# Main_Board.net
KiCad netlist of a schematic drawn in Altium Designer
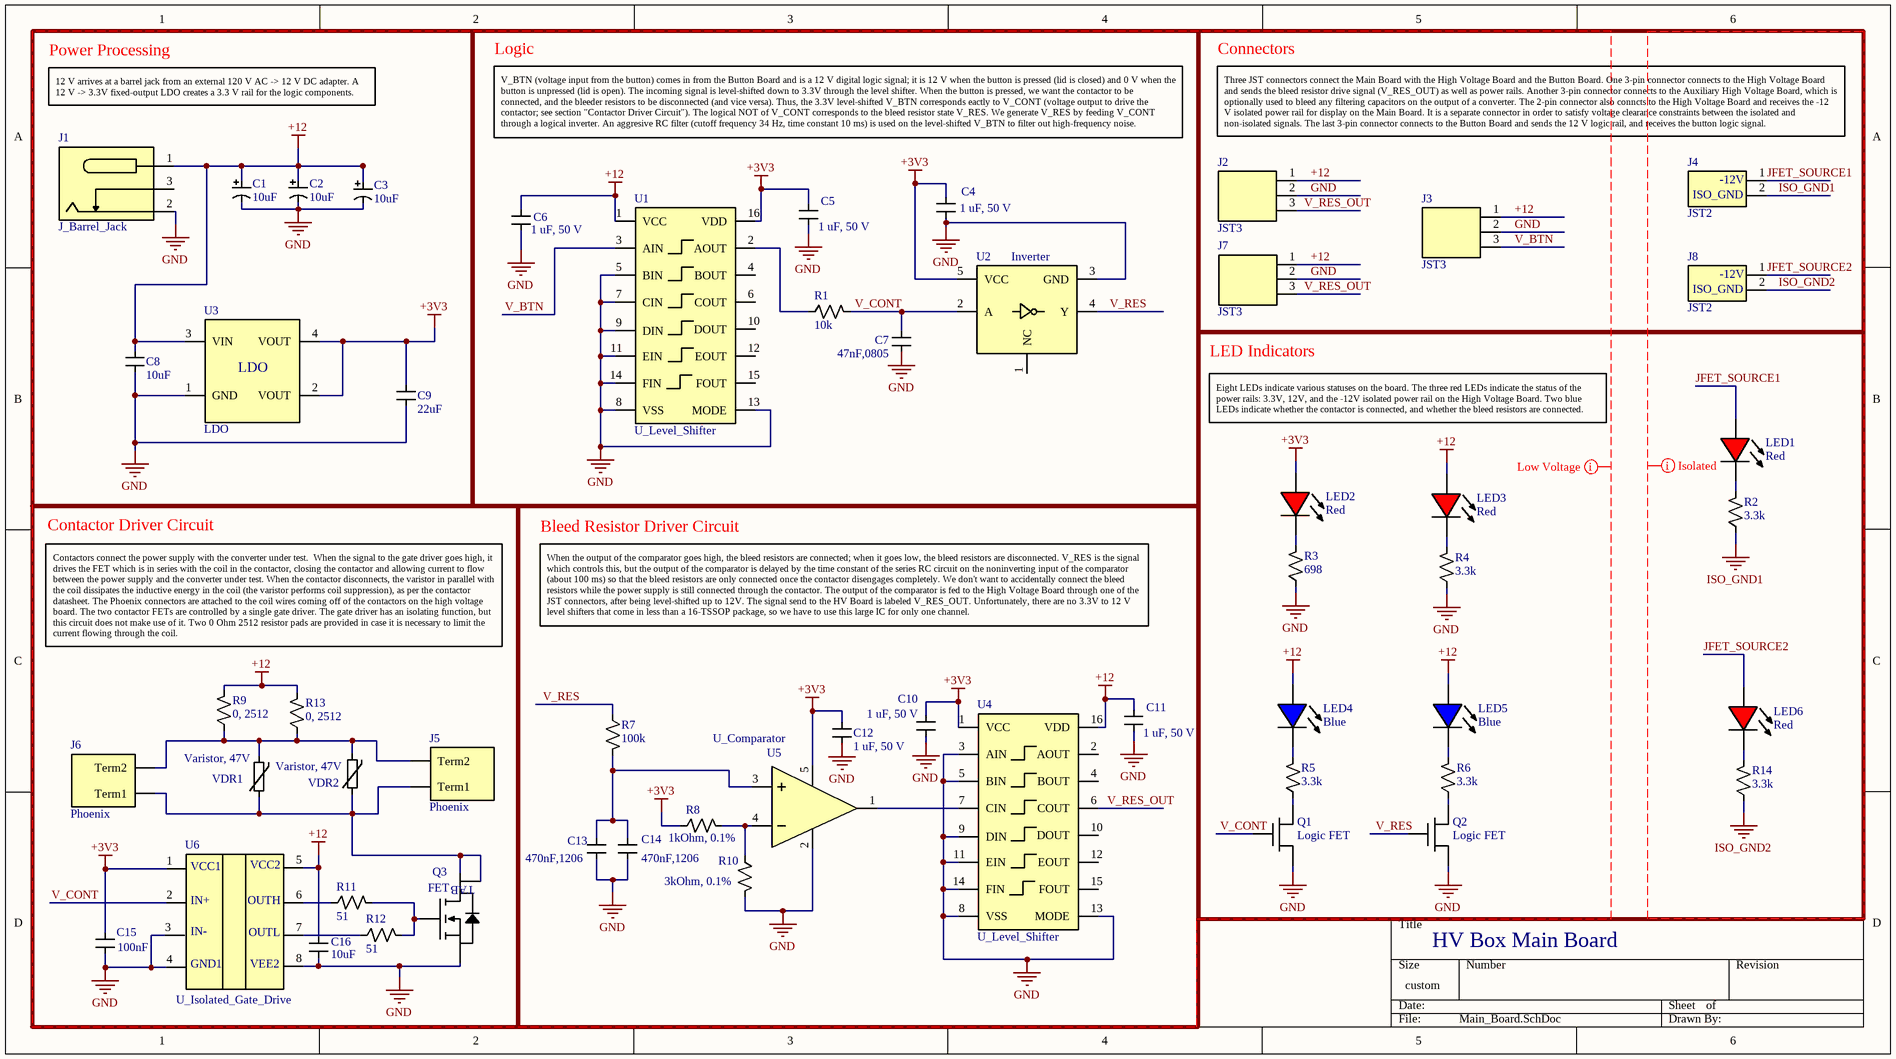
[diagram p0: Main_Board.SchDoc]

(export (version "E")
  (design (tool "Eeschema 10.0.6"))
  (components
    (comp (ref "C1")
      (value "10uF")
      (footprint "ALUM_CAP")
      (description "Capacitor SMD Aluminum Electrolytic 10 uF")
      (libsource (lib "Load_Bank_New_IntLib") (part "C_10uF_AlElec"))
    )
    (comp (ref "C2")
      (value "10uF")
      (footprint "ALUM_CAP")
      (description "Capacitor SMD Aluminum Electrolytic 10 uF")
      (libsource (lib "Load_Bank_New_IntLib") (part "C_10uF_AlElec"))
    )
    (comp (ref "C3")
      (value "10uF")
      (footprint "ALUM_CAP")
      (description "Capacitor SMD Aluminum Electrolytic 10 uF")
      (libsource (lib "Load_Bank_New_IntLib") (part "C_10uF_AlElec"))
    )
    (comp (ref "C4")
      (value "1 uF, 50 V")
      (footprint "0603_CAP")
      (description "Capacitor SMD MLCC 1 uF, 0603, 50 V")
      (libsource (lib "HV_Box_IntLib") (part "C_1uF_0603"))
    )
    (comp (ref "C5")
      (value "1 uF, 50 V")
      (footprint "0603_CAP")
      (description "Capacitor SMD MLCC 1 uF, 0603, 50 V")
      (libsource (lib "HV_Box_IntLib") (part "C_1uF_0603"))
    )
    (comp (ref "C6")
      (value "1 uF, 50 V")
      (footprint "0603_CAP")
      (description "Capacitor SMD MLCC 1 uF, 0603, 50 V")
      (libsource (lib "HV_Box_IntLib") (part "C_1uF_0603"))
    )
    (comp (ref "C7")
      (value "47nF,0805")
      (footprint "0805_CAP")
      (description "Capacitor SMD MLCC 47 nF 0805, C0G/NP0")
      (libsource (lib "HV_Box_IntLib") (part "C_47nF_0805"))
    )
    (comp (ref "C8")
      (value "10uF")
      (footprint "0805_CAP")
      (description "Capacitor SMD MLCC 10 uF 0805")
      (libsource (lib "Load_Bank_New_IntLib") (part "C_10uF_0805"))
    )
    (comp (ref "C9")
      (value "22uF")
      (footprint "1206_CAP")
      (description "Capacitor SMD MLCC 22 uF 25 V 1206")
      (libsource (lib "Load_Bank_New_IntLib") (part "C_22uF_1206"))
    )
    (comp (ref "C10")
      (value "1 uF, 50 V")
      (footprint "0603_CAP")
      (description "Capacitor SMD MLCC 1 uF, 0603, 50 V")
      (libsource (lib "HV_Box_IntLib") (part "C_1uF_0603"))
    )
    (comp (ref "C11")
      (value "1 uF, 50 V")
      (footprint "0603_CAP")
      (description "Capacitor SMD MLCC 1 uF, 0603, 50 V")
      (libsource (lib "HV_Box_IntLib") (part "C_1uF_0603"))
    )
    (comp (ref "C12")
      (value "1 uF, 50 V")
      (footprint "0603_CAP")
      (description "Capacitor SMD MLCC 1 uF, 0603, 50 V")
      (libsource (lib "HV_Box_IntLib") (part "C_1uF_0603"))
    )
    (comp (ref "C13")
      (value "470nF,1206")
      (footprint "1206_CAP")
      (description "Capacitor SMD MLCC 470 nF 1206, C0G/NP0")
      (libsource (lib "HV_Box_IntLib") (part "C_470nF_1206"))
    )
    (comp (ref "C14")
      (value "470nF,1206")
      (footprint "1206_CAP")
      (description "Capacitor SMD MLCC 470 nF 1206, C0G/NP0")
      (libsource (lib "HV_Box_IntLib") (part "C_470nF_1206"))
    )
    (comp (ref "C15")
      (value "100nF")
      (footprint "0603_CAP")
      (description "Capacitor SMD MLCC 100 nF 0603")
      (libsource (lib "Load_Bank_New_IntLib") (part "C_100nF_0603"))
    )
    (comp (ref "C16")
      (value "10uF")
      (footprint "0805_CAP")
      (description "Capacitor SMD MLCC 10 uF 0805")
      (libsource (lib "Load_Bank_New_IntLib") (part "C_10uF_0805"))
    )
    (comp (ref "J1")
      (value "J_Barrel_Jack")
      (footprint "PWR_JACK")
      (description "Jack 12 V Barrel Jack Power Plug")
      (libsource (lib "Load_Bank_New_IntLib") (part "J_Barrel_Jack"))
    )
    (comp (ref "J2")
      (value "JST3")
      (footprint "JST_3")
      (description "Jack JST 3-pin")
      (libsource (lib "HV_Box_IntLib") (part "J_JST_3"))
    )
    (comp (ref "J3")
      (value "JST3")
      (footprint "JST_3")
      (description "Jack JST 3-pin")
      (libsource (lib "HV_Box_IntLib") (part "J_JST_3"))
    )
    (comp (ref "J4")
      (value "JST2")
      (footprint "JST_2")
      (description "Jack JST 2-pin")
      (libsource (lib "HV_Box_IntLib") (part "J_JST_2"))
    )
    (comp (ref "J5")
      (value "Phoenix")
      (footprint "PHOENIX_CONNECTOR_SMALL")
      (description "Phoenix Connector, Female, 2 position, 2 A, 250 V per position")
      (libsource (lib "HV_Box_IntLib") (part "J_Phoenix_Small"))
    )
    (comp (ref "J6")
      (value "Phoenix")
      (footprint "PHOENIX_CONNECTOR_SMALL")
      (description "Phoenix Connector, Female, 2 position, 2 A, 250 V per position")
      (libsource (lib "") (part "J_Phoenix_Small_1"))
    )
    (comp (ref "J7")
      (value "JST3")
      (footprint "JST_3")
      (description "Jack JST 3-pin")
      (libsource (lib "HV_Box_IntLib") (part "J_JST_3"))
    )
    (comp (ref "J8")
      (value "JST2")
      (footprint "JST_2")
      (description "Jack JST 2-pin")
      (libsource (lib "HV_Box_IntLib") (part "J_JST_2"))
    )
    (comp (ref "LED1")
      (value "Red")
      (footprint "0603_LED")
      (description "LED SMD 0603 Red")
      (libsource (lib "Load_Bank_New_IntLib") (part "LED_0603_Red"))
    )
    (comp (ref "LED2")
      (value "Red")
      (footprint "0603_LED")
      (description "LED SMD 0603 Red")
      (libsource (lib "Load_Bank_New_IntLib") (part "LED_0603_Red"))
    )
    (comp (ref "LED3")
      (value "Red")
      (footprint "0603_LED")
      (description "LED SMD 0603 Red")
      (libsource (lib "Load_Bank_New_IntLib") (part "LED_0603_Red"))
    )
    (comp (ref "LED4")
      (value "Blue")
      (footprint "0603_LED")
      (description "LED SMD 0603 Blue")
      (libsource (lib "Load_Bank_New_IntLib") (part "LED_0603_Blue"))
    )
    (comp (ref "LED5")
      (value "Blue")
      (footprint "0603_LED")
      (description "LED SMD 0603 Blue")
      (libsource (lib "Load_Bank_New_IntLib") (part "LED_0603_Blue"))
    )
    (comp (ref "LED6")
      (value "Red")
      (footprint "0603_LED")
      (description "LED SMD 0603 Red")
      (libsource (lib "Load_Bank_New_IntLib") (part "LED_0603_Red"))
    )
    (comp (ref "Q1")
      (value "Logic FET")
      (footprint "SOT23")
      (description "N-Channel Logic FET SOT23-3")
      (libsource (lib "Load_Bank_New_IntLib") (part "Q_NFET"))
    )
    (comp (ref "Q2")
      (value "Logic FET")
      (footprint "SOT23")
      (description "N-Channel Logic FET SOT23-3")
      (libsource (lib "Load_Bank_New_IntLib") (part "Q_NFET"))
    )
    (comp (ref "Q3")
      (value "FET")
      (footprint "TO-220")
      (description "N-Channel Power FET 150 V 100 A")
      (libsource (lib "HV_Box_IntLib") (part "Q_NFET_150V"))
    )
    (comp (ref "R1")
      (value "10k")
      (footprint "0603_RES")
      (description "Resistor 10 kOhm 0603 1%")
      (libsource (lib "Load_Bank_New_IntLib") (part "R_10kOhm_0603_1%"))
    )
    (comp (ref "R2")
      (value "3.3k")
      (footprint "0603_RES")
      (description "Resistor 3.3 kOhm 0603 1%")
      (libsource (lib "Load_Bank_New_IntLib") (part "R_3300Ohm_0603_1%"))
    )
    (comp (ref "R3")
      (value "698")
      (footprint "0603_RES")
      (description "Resistor 698 Ohm 0603 0.5%")
      (libsource (lib "Load_Bank_New_IntLib") (part "R_698Ohm_0603_0.5%"))
    )
    (comp (ref "R4")
      (value "3.3k")
      (footprint "0603_RES")
      (description "Resistor 3.3 kOhm 0603 1%")
      (libsource (lib "Load_Bank_New_IntLib") (part "R_3300Ohm_0603_1%"))
    )
    (comp (ref "R5")
      (value "3.3k")
      (footprint "0603_RES")
      (description "Resistor 3.3 kOhm 0603 1%")
      (libsource (lib "Load_Bank_New_IntLib") (part "R_3300Ohm_0603_1%"))
    )
    (comp (ref "R6")
      (value "3.3k")
      (footprint "0603_RES")
      (description "Resistor 3.3 kOhm 0603 1%")
      (libsource (lib "Load_Bank_New_IntLib") (part "R_3300Ohm_0603_1%"))
    )
    (comp (ref "R7")
      (value "100k")
      (footprint "0603_RES")
      (description "Resistor 100 kOhm 0603 0.5%")
      (libsource (lib "Load_Bank_New_IntLib") (part "R_100kOhm_0603_0.5%"))
    )
    (comp (ref "R8")
      (value "1kOhm, 0.1%")
      (footprint "0603_RES")
      (description "Resistor 1 kOhm 0603 0.1%")
      (libsource (lib "HV_Box_IntLib") (part "R_1kOhm_0603_0.1%"))
    )
    (comp (ref "R9")
      (value "0, 2512")
      (footprint "2512_RES")
      (description "Resistor 0 Ohm 2512")
      (libsource (lib "HV_Box_IntLib") (part "R_0Ohm_2512"))
    )
    (comp (ref "R10")
      (value "3kOhm, 0.1%")
      (footprint "0603_RES")
      (description "Resistor 3 kOhm 0603 0.1%")
      (libsource (lib "HV_Box_IntLib") (part "R_3kOhm_0603_0.1%_1"))
    )
    (comp (ref "R11")
      (value "51")
      (footprint "0603_RES")
      (description "Resistor 51 Ohm 0603 1%")
      (libsource (lib "Load_Bank_New_IntLib") (part "R_51Ohm_0603_1%"))
    )
    (comp (ref "R12")
      (value "51")
      (footprint "0603_RES")
      (description "Resistor 51 Ohm 0603 1%")
      (libsource (lib "Load_Bank_New_IntLib") (part "R_51Ohm_0603_1%"))
    )
    (comp (ref "R13")
      (value "0, 2512")
      (footprint "2512_RES")
      (description "Resistor 0 Ohm 2512")
      (libsource (lib "HV_Box_IntLib") (part "R_0Ohm_2512"))
    )
    (comp (ref "R14")
      (value "3.3k")
      (footprint "0603_RES")
      (description "Resistor 3.3 kOhm 0603 1%")
      (libsource (lib "Load_Bank_New_IntLib") (part "R_3300Ohm_0603_1%"))
    )
    (comp (ref "U1")
      (value "U_Level_Shifter")
      (footprint "TSSOP-16")
      (description "IC 6-in-1 level shifter")
      (libsource (lib "Load_Bank_New_IntLib") (part "U_Level_Shifter"))
    )
    (comp (ref "U2")
      (value "Inverter")
      (footprint "SOT23-5")
      (description "IC Single Inverter")
      (libsource (lib "HV_Box_IntLib") (part "U_Inverter_1"))
    )
    (comp (ref "U3")
      (value "LDO")
      (footprint "SOT223-3")
      (description "IC LDO Fixed Output 3.3V, input up to 12 V, SOT223-3 Package")
      (libsource (lib "HV_Box_IntLib") (part "U_LDO_12V_3V3"))
    )
    (comp (ref "U4")
      (value "U_Level_Shifter")
      (footprint "TSSOP-16")
      (description "IC 6-in-1 level shifter")
      (libsource (lib "Load_Bank_New_IntLib") (part "U_Level_Shifter"))
    )
    (comp (ref "U5")
      (value "U_Comparator")
      (footprint "SC70")
      (description "IC 3.3V Comparator Push-Pull")
      (libsource (lib "HV_Box_IntLib") (part "U_Comparator"))
    )
    (comp (ref "U6")
      (value "U_Isolated_Gate_Drive")
      (footprint "GATE_DRIVER")
      (description "IC Isolated Gate Drive 3-15 V Output Supply Split Output")
      (libsource (lib "Load_Bank_New_IntLib") (part "U_Isolated_Gate_Drive"))
    )
    (comp (ref "VDR1")
      (value "Varistor, 47V")
      (footprint "VARISTOR")
      (description "Varistor, 47 V, 500 A, 10 mm Disc Through-Hole")
      (libsource (lib "HV_Box_IntLib") (part "VDR_47V"))
    )
    (comp (ref "VDR2")
      (value "Varistor, 47V")
      (footprint "VARISTOR")
      (description "Varistor, 47 V, 500 A, 10 mm Disc Through-Hole")
      (libsource (lib "HV_Box_IntLib") (part "VDR_47V"))
    )
  )
  (nets
    (net (code "1") (name "+3V3") (class "Default")
      (node (ref "C10") (pin "2") (pintype "passive"))
      (node (ref "C12") (pin "2") (pintype "passive"))
      (node (ref "C15") (pin "2") (pintype "passive"))
      (node (ref "C4") (pin "2") (pintype "passive"))
      (node (ref "C5") (pin "2") (pintype "passive"))
      (node (ref "C9") (pin "2") (pintype "passive"))
      (node (ref "LED2") (pin "2") (pintype "passive"))
      (node (ref "R8") (pin "1") (pintype "passive"))
      (node (ref "U1") (pin "16") (pinfunction "VDD_16") (pintype "passive"))
      (node (ref "U2") (pin "5") (pinfunction "VCC_5") (pintype "passive"))
      (node (ref "U3") (pin "2") (pinfunction "VOUT_2") (pintype "passive"))
      (node (ref "U3") (pin "4") (pinfunction "VOUT_4") (pintype "passive"))
      (node (ref "U4") (pin "1") (pinfunction "VCC_1") (pintype "passive"))
      (node (ref "U5") (pin "5") (pinfunction "VDD_5") (pintype "passive"))
      (node (ref "U6") (pin "1") (pinfunction "VCC1_1") (pintype "passive"))
    )
    (net (code "2") (name "+12") (class "Default")
      (node (ref "C1") (pin "2") (pintype "passive"))
      (node (ref "C11") (pin "2") (pintype "passive"))
      (node (ref "C16") (pin "2") (pintype "passive"))
      (node (ref "C2") (pin "2") (pintype "passive"))
      (node (ref "C3") (pin "2") (pintype "passive"))
      (node (ref "C6") (pin "2") (pintype "passive"))
      (node (ref "C8") (pin "2") (pintype "passive"))
      (node (ref "J1") (pin "1") (pinfunction "GND_1") (pintype "passive"))
      (node (ref "J2") (pin "1") (pinfunction "Sig1_1") (pintype "passive"))
      (node (ref "J3") (pin "1") (pinfunction "Sig1_1") (pintype "passive"))
      (node (ref "J7") (pin "1") (pinfunction "Sig1_1") (pintype "passive"))
      (node (ref "LED3") (pin "2") (pintype "passive"))
      (node (ref "LED4") (pin "2") (pintype "passive"))
      (node (ref "LED5") (pin "2") (pintype "passive"))
      (node (ref "R13") (pin "2") (pintype "passive"))
      (node (ref "R9") (pin "2") (pintype "passive"))
      (node (ref "U1") (pin "1") (pinfunction "VCC_1") (pintype "passive"))
      (node (ref "U3") (pin "3") (pinfunction "VIN_3") (pintype "passive"))
      (node (ref "U4") (pin "16") (pinfunction "VDD_16") (pintype "passive"))
      (node (ref "U6") (pin "5") (pinfunction "VCC2_5") (pintype "passive"))
    )
    (net (code "3") (name "/JFET_SOURCE1") (class "Default")
      (node (ref "J4") (pin "1") (pinfunction "Sig1_1") (pintype "passive"))
      (node (ref "LED1") (pin "2") (pintype "passive"))
    )
    (net (code "4") (name "/JFET_SOURCE2") (class "Default")
      (node (ref "J8") (pin "1") (pinfunction "Sig1_1") (pintype "passive"))
      (node (ref "LED6") (pin "2") (pintype "passive"))
    )
    (net (code "5") (name "/V_BTN") (class "Default")
      (node (ref "J3") (pin "3") (pinfunction "NC_3") (pintype "passive"))
      (node (ref "U1") (pin "3") (pinfunction "AIN_3") (pintype "passive"))
    )
    (net (code "6") (name "/V_CONT") (class "Default")
      (node (ref "C7") (pin "2") (pintype "passive"))
      (node (ref "Q1") (pin "2") (pinfunction "G_2") (pintype "passive"))
      (node (ref "R1") (pin "2") (pintype "passive"))
      (node (ref "U2") (pin "2") (pinfunction "A_2") (pintype "passive"))
      (node (ref "U6") (pin "2") (pinfunction "IN+_2") (pintype "passive"))
    )
    (net (code "7") (name "/V_RES") (class "Default")
      (node (ref "Q2") (pin "2") (pinfunction "G_2") (pintype "passive"))
      (node (ref "R7") (pin "1") (pintype "passive"))
      (node (ref "U2") (pin "4") (pinfunction "Y_4") (pintype "passive"))
    )
    (net (code "8") (name "/V_RES_OUT") (class "Default")
      (node (ref "J2") (pin "3") (pinfunction "NC_3") (pintype "passive"))
      (node (ref "J7") (pin "3") (pinfunction "NC_3") (pintype "passive"))
      (node (ref "U4") (pin "6") (pinfunction "COUT_6") (pintype "passive"))
    )
    (net (code "9") (name "GND") (class "Default")
      (node (ref "C1") (pin "1") (pintype "passive"))
      (node (ref "C10") (pin "1") (pintype "passive"))
      (node (ref "C11") (pin "1") (pintype "passive"))
      (node (ref "C12") (pin "1") (pintype "passive"))
      (node (ref "C13") (pin "1") (pintype "passive"))
      (node (ref "C14") (pin "1") (pintype "passive"))
      (node (ref "C15") (pin "1") (pintype "passive"))
      (node (ref "C16") (pin "1") (pintype "passive"))
      (node (ref "C2") (pin "1") (pintype "passive"))
      (node (ref "C3") (pin "1") (pintype "passive"))
      (node (ref "C4") (pin "1") (pintype "passive"))
      (node (ref "C5") (pin "1") (pintype "passive"))
      (node (ref "C6") (pin "1") (pintype "passive"))
      (node (ref "C7") (pin "1") (pintype "passive"))
      (node (ref "C8") (pin "1") (pintype "passive"))
      (node (ref "C9") (pin "1") (pintype "passive"))
      (node (ref "J1") (pin "2") (pinfunction "PWR_JACK_2") (pintype "passive"))
      (node (ref "J2") (pin "2") (pinfunction "Sig2_2") (pintype "passive"))
      (node (ref "J3") (pin "2") (pinfunction "Sig2_2") (pintype "passive"))
      (node (ref "J7") (pin "2") (pinfunction "Sig2_2") (pintype "passive"))
      (node (ref "Q1") (pin "3") (pinfunction "S_3") (pintype "passive"))
      (node (ref "Q2") (pin "3") (pinfunction "S_3") (pintype "passive"))
      (node (ref "Q3") (pin "3") (pinfunction "S_3") (pintype "passive"))
      (node (ref "R10") (pin "2") (pintype "passive"))
      (node (ref "R3") (pin "1") (pintype "passive"))
      (node (ref "R4") (pin "1") (pintype "passive"))
      (node (ref "U1") (pin "11") (pinfunction "EIN_11") (pintype "passive"))
      (node (ref "U1") (pin "13") (pinfunction "MODE_13") (pintype "passive"))
      (node (ref "U1") (pin "14") (pinfunction "FIN_14") (pintype "passive"))
      (node (ref "U1") (pin "5") (pinfunction "BIN_5") (pintype "passive"))
      (node (ref "U1") (pin "7") (pinfunction "CIN_7") (pintype "passive"))
      (node (ref "U1") (pin "8") (pinfunction "VSS_8") (pintype "passive"))
      (node (ref "U1") (pin "9") (pinfunction "DIN_9") (pintype "passive"))
      (node (ref "U2") (pin "3") (pinfunction "GND_3") (pintype "passive"))
      (node (ref "U3") (pin "1") (pinfunction "GND_1") (pintype "passive"))
      (node (ref "U4") (pin "11") (pinfunction "EIN_11") (pintype "passive"))
      (node (ref "U4") (pin "13") (pinfunction "MODE_13") (pintype "passive"))
      (node (ref "U4") (pin "14") (pinfunction "FIN_14") (pintype "passive"))
      (node (ref "U4") (pin "3") (pinfunction "AIN_3") (pintype "passive"))
      (node (ref "U4") (pin "5") (pinfunction "BIN_5") (pintype "passive"))
      (node (ref "U4") (pin "8") (pinfunction "VSS_8") (pintype "passive"))
      (node (ref "U4") (pin "9") (pinfunction "DIN_9") (pintype "passive"))
      (node (ref "U5") (pin "2") (pinfunction "GND_2") (pintype "passive"))
      (node (ref "U6") (pin "3") (pinfunction "IN-_3") (pintype "passive"))
      (node (ref "U6") (pin "4") (pinfunction "GND1_4") (pintype "passive"))
      (node (ref "U6") (pin "8") (pinfunction "VEE2_8") (pintype "passive"))
    )
    (net (code "10") (name "ISO_GND1") (class "Default")
      (node (ref "J4") (pin "2") (pinfunction "Sig2_2") (pintype "passive"))
      (node (ref "R2") (pin "1") (pintype "passive"))
    )
    (net (code "11") (name "ISO_GND2") (class "Default")
      (node (ref "J8") (pin "2") (pinfunction "Sig2_2") (pintype "passive"))
      (node (ref "R14") (pin "1") (pintype "passive"))
    )
    (net (code "12") (name "Net-(J5-Term1)") (class "Default")
      (node (ref "J5") (pin "1") (pinfunction "Term1_1") (pintype "passive"))
      (node (ref "J6") (pin "1") (pinfunction "Term1_1") (pintype "passive"))
      (node (ref "Q3") (pin "2") (pinfunction "D_2") (pintype "passive"))
      (node (ref "Q3") (pin "4") (pinfunction "TAB_4") (pintype "passive"))
      (node (ref "VDR1") (pin "1") (pintype "passive"))
      (node (ref "VDR2") (pin "1") (pintype "passive"))
    )
    (net (code "13") (name "Net-(J5-Term2)") (class "Default")
      (node (ref "J5") (pin "2") (pinfunction "Term2_2") (pintype "passive"))
      (node (ref "J6") (pin "2") (pinfunction "Term2_2") (pintype "passive"))
      (node (ref "R13") (pin "1") (pintype "passive"))
      (node (ref "R9") (pin "1") (pintype "passive"))
      (node (ref "VDR1") (pin "2") (pintype "passive"))
      (node (ref "VDR2") (pin "2") (pintype "passive"))
    )
    (net (code "14") (name "Net-(LED1-Pad1)") (class "Default")
      (node (ref "LED1") (pin "1") (pintype "passive"))
      (node (ref "R2") (pin "2") (pintype "passive"))
    )
    (net (code "15") (name "Net-(LED2-Pad1)") (class "Default")
      (node (ref "LED2") (pin "1") (pintype "passive"))
      (node (ref "R3") (pin "2") (pintype "passive"))
    )
    (net (code "16") (name "Net-(LED3-Pad1)") (class "Default")
      (node (ref "LED3") (pin "1") (pintype "passive"))
      (node (ref "R4") (pin "2") (pintype "passive"))
    )
    (net (code "17") (name "Net-(LED4-Pad1)") (class "Default")
      (node (ref "LED4") (pin "1") (pintype "passive"))
      (node (ref "R5") (pin "2") (pintype "passive"))
    )
    (net (code "18") (name "Net-(LED5-Pad1)") (class "Default")
      (node (ref "LED5") (pin "1") (pintype "passive"))
      (node (ref "R6") (pin "2") (pintype "passive"))
    )
    (net (code "19") (name "Net-(LED6-Pad1)") (class "Default")
      (node (ref "LED6") (pin "1") (pintype "passive"))
      (node (ref "R14") (pin "2") (pintype "passive"))
    )
    (net (code "20") (name "Net-(Q1-D)") (class "Default")
      (node (ref "Q1") (pin "1") (pinfunction "D_1") (pintype "passive"))
      (node (ref "R5") (pin "1") (pintype "passive"))
    )
    (net (code "21") (name "Net-(Q2-D)") (class "Default")
      (node (ref "Q2") (pin "1") (pinfunction "D_1") (pintype "passive"))
      (node (ref "R6") (pin "1") (pintype "passive"))
    )
    (net (code "22") (name "Net-(Q3-G)") (class "Default")
      (node (ref "Q3") (pin "1") (pinfunction "G_1") (pintype "passive"))
      (node (ref "R11") (pin "2") (pintype "passive"))
      (node (ref "R12") (pin "2") (pintype "passive"))
    )
    (net (code "23") (name "Net-(U1-AOUT)") (class "Default")
      (node (ref "R1") (pin "1") (pintype "passive"))
      (node (ref "U1") (pin "2") (pinfunction "AOUT_2") (pintype "passive"))
    )
    (net (code "24") (name "Net-(U4-CIN)") (class "Default")
      (node (ref "U4") (pin "7") (pinfunction "CIN_7") (pintype "passive"))
      (node (ref "U5") (pin "1") (pinfunction "Out_1") (pintype "passive"))
    )
    (net (code "25") (name "Net-(U5-V+)") (class "Default")
      (node (ref "C13") (pin "2") (pintype "passive"))
      (node (ref "C14") (pin "2") (pintype "passive"))
      (node (ref "R7") (pin "2") (pintype "passive"))
      (node (ref "U5") (pin "3") (pinfunction "V+_3") (pintype "passive"))
    )
    (net (code "26") (name "Net-(U5-V-)") (class "Default")
      (node (ref "R10") (pin "1") (pintype "passive"))
      (node (ref "R8") (pin "2") (pintype "passive"))
      (node (ref "U5") (pin "4") (pinfunction "V-_4") (pintype "passive"))
    )
    (net (code "27") (name "Net-(U6-OUTH)") (class "Default")
      (node (ref "R11") (pin "1") (pintype "passive"))
      (node (ref "U6") (pin "6") (pinfunction "OUTH_6") (pintype "passive"))
    )
    (net (code "28") (name "Net-(U6-OUTL)") (class "Default")
      (node (ref "R12") (pin "1") (pintype "passive"))
      (node (ref "U6") (pin "7") (pinfunction "OUTL_7") (pintype "passive"))
    )
    (net (code "29") (name "unconnected-(J1-PWR_BAT-Pad3)") (class "Default")
      (node (ref "J1") (pin "3") (pinfunction "PWR_BAT_3") (pintype "passive"))
    )
    (net (code "30") (name "unconnected-(U1-BOUT-Pad4)") (class "Default")
      (node (ref "U1") (pin "4") (pinfunction "BOUT_4") (pintype "passive"))
    )
    (net (code "31") (name "unconnected-(U1-COUT-Pad6)") (class "Default")
      (node (ref "U1") (pin "6") (pinfunction "COUT_6") (pintype "passive"))
    )
    (net (code "32") (name "unconnected-(U1-DOUT-Pad10)") (class "Default")
      (node (ref "U1") (pin "10") (pinfunction "DOUT_10") (pintype "passive"))
    )
    (net (code "33") (name "unconnected-(U1-EOUT-Pad12)") (class "Default")
      (node (ref "U1") (pin "12") (pinfunction "EOUT_12") (pintype "passive"))
    )
    (net (code "34") (name "unconnected-(U1-FOUT-Pad15)") (class "Default")
      (node (ref "U1") (pin "15") (pinfunction "FOUT_15") (pintype "passive"))
    )
    (net (code "35") (name "unconnected-(U2-NC-Pad1)") (class "Default")
      (node (ref "U2") (pin "1") (pinfunction "NC_1") (pintype "passive"))
    )
    (net (code "36") (name "unconnected-(U4-AOUT-Pad2)") (class "Default")
      (node (ref "U4") (pin "2") (pinfunction "AOUT_2") (pintype "passive"))
    )
    (net (code "37") (name "unconnected-(U4-BOUT-Pad4)") (class "Default")
      (node (ref "U4") (pin "4") (pinfunction "BOUT_4") (pintype "passive"))
    )
    (net (code "38") (name "unconnected-(U4-DOUT-Pad10)") (class "Default")
      (node (ref "U4") (pin "10") (pinfunction "DOUT_10") (pintype "passive"))
    )
    (net (code "39") (name "unconnected-(U4-EOUT-Pad12)") (class "Default")
      (node (ref "U4") (pin "12") (pinfunction "EOUT_12") (pintype "passive"))
    )
    (net (code "40") (name "unconnected-(U4-FOUT-Pad15)") (class "Default")
      (node (ref "U4") (pin "15") (pinfunction "FOUT_15") (pintype "passive"))
    )
  )
)
